# RAM.net
KiCad netlist of a schematic drawn in Altium Designer
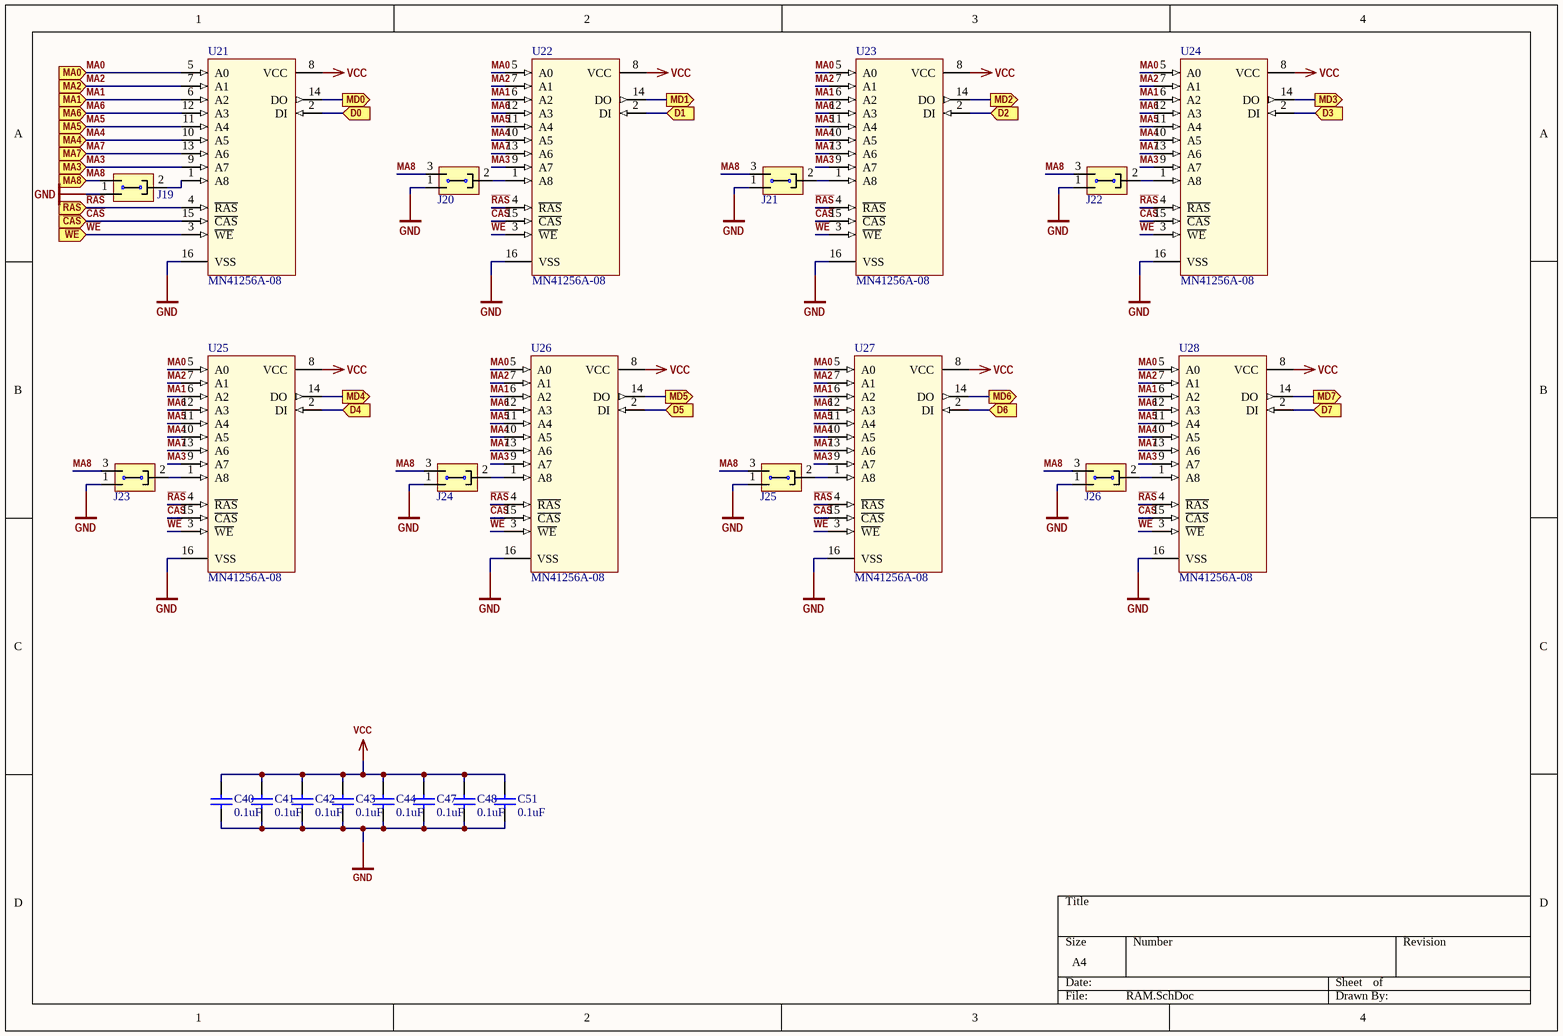
[diagram p0: RAM.SchDoc]

(export (version "E")
  (design (tool "Eeschema 10.0.6"))
  (components
    (comp (ref "C40")
      (value "0.1uF")
      (footprint "RAD-0.3")
      (description "Capacitor")
      (fields (field (name "Comment") "Cap") (field (name "PUBLISHER") "Altium Limited"))
      (libsource (lib "Lenin") (part "Cap"))
    )
    (comp (ref "C41")
      (value "0.1uF")
      (footprint "RAD-0.3")
      (description "Capacitor")
      (fields (field (name "Comment") "Cap") (field (name "PUBLISHER") "Altium Limited"))
      (libsource (lib "Lenin") (part "Cap"))
    )
    (comp (ref "C42")
      (value "0.1uF")
      (footprint "RAD-0.3")
      (description "Capacitor")
      (fields (field (name "Comment") "Cap") (field (name "PUBLISHER") "Altium Limited"))
      (libsource (lib "Lenin") (part "Cap"))
    )
    (comp (ref "C43")
      (value "0.1uF")
      (footprint "RAD-0.3")
      (description "Capacitor")
      (fields (field (name "Comment") "Cap") (field (name "PUBLISHER") "Altium Limited"))
      (libsource (lib "Lenin") (part "Cap"))
    )
    (comp (ref "C44")
      (value "0.1uF")
      (footprint "RAD-0.3")
      (description "Capacitor")
      (fields (field (name "Comment") "Cap") (field (name "PUBLISHER") "Altium Limited"))
      (libsource (lib "Lenin") (part "Cap"))
    )
    (comp (ref "C47")
      (value "0.1uF")
      (footprint "RAD-0.3")
      (description "Capacitor")
      (fields (field (name "Comment") "Cap") (field (name "PUBLISHER") "Altium Limited"))
      (libsource (lib "Lenin") (part "Cap"))
    )
    (comp (ref "C48")
      (value "0.1uF")
      (footprint "RAD-0.3")
      (description "Capacitor")
      (fields (field (name "Comment") "Cap") (field (name "PUBLISHER") "Altium Limited"))
      (libsource (lib "Lenin") (part "Cap"))
    )
    (comp (ref "C51")
      (value "0.1uF")
      (footprint "RAD-0.3")
      (description "Capacitor")
      (fields (field (name "Comment") "Cap") (field (name "PUBLISHER") "Altium Limited"))
      (libsource (lib "Lenin") (part "Cap"))
    )
    (comp (ref "J19")
      (value "Jump3")
      (footprint "Miscellaneous Connectors:MHDR1X3")
      (libsource (lib "Lenin") (part "Jump3"))
    )
    (comp (ref "J20")
      (value "Jump3")
      (footprint "Miscellaneous Connectors:MHDR1X3")
      (libsource (lib "Lenin") (part "Jump3"))
    )
    (comp (ref "J21")
      (value "Jump3")
      (footprint "Miscellaneous Connectors:MHDR1X3")
      (libsource (lib "Lenin") (part "Jump3"))
    )
    (comp (ref "J22")
      (value "Jump3")
      (footprint "Miscellaneous Connectors:MHDR1X3")
      (libsource (lib "Lenin") (part "Jump3"))
    )
    (comp (ref "J23")
      (value "Jump3")
      (footprint "Miscellaneous Connectors:MHDR1X3")
      (libsource (lib "Lenin") (part "Jump3"))
    )
    (comp (ref "J24")
      (value "Jump3")
      (footprint "Miscellaneous Connectors:MHDR1X3")
      (libsource (lib "Lenin") (part "Jump3"))
    )
    (comp (ref "J25")
      (value "Jump3")
      (footprint "Miscellaneous Connectors:MHDR1X3")
      (libsource (lib "Lenin") (part "Jump3"))
    )
    (comp (ref "J26")
      (value "Jump3")
      (footprint "Miscellaneous Connectors:MHDR1X3")
      (libsource (lib "Lenin") (part "Jump3"))
    )
    (comp (ref "U21")
      (value "MN41256A-08")
      (footprint "Panasonic:DIP16")
      (libsource (lib "Panasonic") (part "MN41256A-08"))
    )
    (comp (ref "U22")
      (value "MN41256A-08")
      (footprint "Panasonic:DIP16")
      (libsource (lib "Panasonic") (part "MN41256A-08"))
    )
    (comp (ref "U23")
      (value "MN41256A-08")
      (footprint "Panasonic:DIP16")
      (libsource (lib "Panasonic") (part "MN41256A-08"))
    )
    (comp (ref "U24")
      (value "MN41256A-08")
      (footprint "Panasonic:DIP16")
      (libsource (lib "Panasonic") (part "MN41256A-08"))
    )
    (comp (ref "U25")
      (value "MN41256A-08")
      (footprint "Panasonic:DIP16")
      (libsource (lib "Panasonic") (part "MN41256A-08"))
    )
    (comp (ref "U26")
      (value "MN41256A-08")
      (footprint "Panasonic:DIP16")
      (libsource (lib "Panasonic") (part "MN41256A-08"))
    )
    (comp (ref "U27")
      (value "MN41256A-08")
      (footprint "Panasonic:DIP16")
      (libsource (lib "Panasonic") (part "MN41256A-08"))
    )
    (comp (ref "U28")
      (value "MN41256A-08")
      (footprint "Panasonic:DIP16")
      (libsource (lib "Panasonic") (part "MN41256A-08"))
    )
  )
  (nets
    (net (code "1") (name "/D0") (class "Default")
      (node (ref "U21") (pin "2") (pinfunction "DI_2") (pintype "input"))
    )
    (net (code "2") (name "/D1") (class "Default")
      (node (ref "U22") (pin "2") (pinfunction "DI_2") (pintype "input"))
    )
    (net (code "3") (name "/D2") (class "Default")
      (node (ref "U23") (pin "2") (pinfunction "DI_2") (pintype "input"))
    )
    (net (code "4") (name "/D3") (class "Default")
      (node (ref "U24") (pin "2") (pinfunction "DI_2") (pintype "input"))
    )
    (net (code "5") (name "/D4") (class "Default")
      (node (ref "U25") (pin "2") (pinfunction "DI_2") (pintype "input"))
    )
    (net (code "6") (name "/D5") (class "Default")
      (node (ref "U26") (pin "2") (pinfunction "DI_2") (pintype "input"))
    )
    (net (code "7") (name "/D6") (class "Default")
      (node (ref "U27") (pin "2") (pinfunction "DI_2") (pintype "input"))
    )
    (net (code "8") (name "/D7") (class "Default")
      (node (ref "U28") (pin "2") (pinfunction "DI_2") (pintype "input"))
    )
    (net (code "9") (name "/MA0") (class "Default")
      (node (ref "U21") (pin "5") (pinfunction "A0_5") (pintype "input"))
      (node (ref "U22") (pin "5") (pinfunction "A0_5") (pintype "input"))
      (node (ref "U23") (pin "5") (pinfunction "A0_5") (pintype "input"))
      (node (ref "U24") (pin "5") (pinfunction "A0_5") (pintype "input"))
      (node (ref "U25") (pin "5") (pinfunction "A0_5") (pintype "input"))
      (node (ref "U26") (pin "5") (pinfunction "A0_5") (pintype "input"))
      (node (ref "U27") (pin "5") (pinfunction "A0_5") (pintype "input"))
      (node (ref "U28") (pin "5") (pinfunction "A0_5") (pintype "input"))
    )
    (net (code "10") (name "/MA1") (class "Default")
      (node (ref "U21") (pin "6") (pinfunction "A2_6") (pintype "input"))
      (node (ref "U22") (pin "6") (pinfunction "A2_6") (pintype "input"))
      (node (ref "U23") (pin "6") (pinfunction "A2_6") (pintype "input"))
      (node (ref "U24") (pin "6") (pinfunction "A2_6") (pintype "input"))
      (node (ref "U25") (pin "6") (pinfunction "A2_6") (pintype "input"))
      (node (ref "U26") (pin "6") (pinfunction "A2_6") (pintype "input"))
      (node (ref "U27") (pin "6") (pinfunction "A2_6") (pintype "input"))
      (node (ref "U28") (pin "6") (pinfunction "A2_6") (pintype "input"))
    )
    (net (code "11") (name "/MA2") (class "Default")
      (node (ref "U21") (pin "7") (pinfunction "A1_7") (pintype "input"))
      (node (ref "U22") (pin "7") (pinfunction "A1_7") (pintype "input"))
      (node (ref "U23") (pin "7") (pinfunction "A1_7") (pintype "input"))
      (node (ref "U24") (pin "7") (pinfunction "A1_7") (pintype "input"))
      (node (ref "U25") (pin "7") (pinfunction "A1_7") (pintype "input"))
      (node (ref "U26") (pin "7") (pinfunction "A1_7") (pintype "input"))
      (node (ref "U27") (pin "7") (pinfunction "A1_7") (pintype "input"))
      (node (ref "U28") (pin "7") (pinfunction "A1_7") (pintype "input"))
    )
    (net (code "12") (name "/MA3") (class "Default")
      (node (ref "U21") (pin "9") (pinfunction "A7_9") (pintype "input"))
      (node (ref "U22") (pin "9") (pinfunction "A7_9") (pintype "input"))
      (node (ref "U23") (pin "9") (pinfunction "A7_9") (pintype "input"))
      (node (ref "U24") (pin "9") (pinfunction "A7_9") (pintype "input"))
      (node (ref "U25") (pin "9") (pinfunction "A7_9") (pintype "input"))
      (node (ref "U26") (pin "9") (pinfunction "A7_9") (pintype "input"))
      (node (ref "U27") (pin "9") (pinfunction "A7_9") (pintype "input"))
      (node (ref "U28") (pin "9") (pinfunction "A7_9") (pintype "input"))
    )
    (net (code "13") (name "/MA4") (class "Default")
      (node (ref "U21") (pin "10") (pinfunction "A5_10") (pintype "input"))
      (node (ref "U22") (pin "10") (pinfunction "A5_10") (pintype "input"))
      (node (ref "U23") (pin "10") (pinfunction "A5_10") (pintype "input"))
      (node (ref "U24") (pin "10") (pinfunction "A5_10") (pintype "input"))
      (node (ref "U25") (pin "10") (pinfunction "A5_10") (pintype "input"))
      (node (ref "U26") (pin "10") (pinfunction "A5_10") (pintype "input"))
      (node (ref "U27") (pin "10") (pinfunction "A5_10") (pintype "input"))
      (node (ref "U28") (pin "10") (pinfunction "A5_10") (pintype "input"))
    )
    (net (code "14") (name "/MA5") (class "Default")
      (node (ref "U21") (pin "11") (pinfunction "A4_11") (pintype "input"))
      (node (ref "U22") (pin "11") (pinfunction "A4_11") (pintype "input"))
      (node (ref "U23") (pin "11") (pinfunction "A4_11") (pintype "input"))
      (node (ref "U24") (pin "11") (pinfunction "A4_11") (pintype "input"))
      (node (ref "U25") (pin "11") (pinfunction "A4_11") (pintype "input"))
      (node (ref "U26") (pin "11") (pinfunction "A4_11") (pintype "input"))
      (node (ref "U27") (pin "11") (pinfunction "A4_11") (pintype "input"))
      (node (ref "U28") (pin "11") (pinfunction "A4_11") (pintype "input"))
    )
    (net (code "15") (name "/MA6") (class "Default")
      (node (ref "U21") (pin "12") (pinfunction "A3_12") (pintype "input"))
      (node (ref "U22") (pin "12") (pinfunction "A3_12") (pintype "input"))
      (node (ref "U23") (pin "12") (pinfunction "A3_12") (pintype "input"))
      (node (ref "U24") (pin "12") (pinfunction "A3_12") (pintype "input"))
      (node (ref "U25") (pin "12") (pinfunction "A3_12") (pintype "input"))
      (node (ref "U26") (pin "12") (pinfunction "A3_12") (pintype "input"))
      (node (ref "U27") (pin "12") (pinfunction "A3_12") (pintype "input"))
      (node (ref "U28") (pin "12") (pinfunction "A3_12") (pintype "input"))
    )
    (net (code "16") (name "/MA7") (class "Default")
      (node (ref "U21") (pin "13") (pinfunction "A6_13") (pintype "input"))
      (node (ref "U22") (pin "13") (pinfunction "A6_13") (pintype "input"))
      (node (ref "U23") (pin "13") (pinfunction "A6_13") (pintype "input"))
      (node (ref "U24") (pin "13") (pinfunction "A6_13") (pintype "input"))
      (node (ref "U25") (pin "13") (pinfunction "A6_13") (pintype "input"))
      (node (ref "U26") (pin "13") (pinfunction "A6_13") (pintype "input"))
      (node (ref "U27") (pin "13") (pinfunction "A6_13") (pintype "input"))
      (node (ref "U28") (pin "13") (pinfunction "A6_13") (pintype "input"))
    )
    (net (code "17") (name "/MA8") (class "Default")
      (node (ref "J19") (pin "3") (pintype "passive"))
      (node (ref "J20") (pin "3") (pintype "passive"))
      (node (ref "J21") (pin "3") (pintype "passive"))
      (node (ref "J22") (pin "3") (pintype "passive"))
      (node (ref "J23") (pin "3") (pintype "passive"))
      (node (ref "J24") (pin "3") (pintype "passive"))
      (node (ref "J25") (pin "3") (pintype "passive"))
      (node (ref "J26") (pin "3") (pintype "passive"))
    )
    (net (code "18") (name "/MD0") (class "Default")
      (node (ref "U21") (pin "14") (pinfunction "DO_14") (pintype "output"))
    )
    (net (code "19") (name "/MD1") (class "Default")
      (node (ref "U22") (pin "14") (pinfunction "DO_14") (pintype "output"))
    )
    (net (code "20") (name "/MD2") (class "Default")
      (node (ref "U23") (pin "14") (pinfunction "DO_14") (pintype "output"))
    )
    (net (code "21") (name "/MD3") (class "Default")
      (node (ref "U24") (pin "14") (pinfunction "DO_14") (pintype "output"))
    )
    (net (code "22") (name "/MD4") (class "Default")
      (node (ref "U25") (pin "14") (pinfunction "DO_14") (pintype "output"))
    )
    (net (code "23") (name "/MD5") (class "Default")
      (node (ref "U26") (pin "14") (pinfunction "DO_14") (pintype "output"))
    )
    (net (code "24") (name "/MD6") (class "Default")
      (node (ref "U27") (pin "14") (pinfunction "DO_14") (pintype "output"))
    )
    (net (code "25") (name "/MD7") (class "Default")
      (node (ref "U28") (pin "14") (pinfunction "DO_14") (pintype "output"))
    )
    (net (code "26") (name "/~{CAS}") (class "Default")
      (node (ref "U21") (pin "15") (pinfunction "~{CAS}_15") (pintype "input"))
      (node (ref "U22") (pin "15") (pinfunction "~{CAS}_15") (pintype "input"))
      (node (ref "U23") (pin "15") (pinfunction "~{CAS}_15") (pintype "input"))
      (node (ref "U24") (pin "15") (pinfunction "~{CAS}_15") (pintype "input"))
      (node (ref "U25") (pin "15") (pinfunction "~{CAS}_15") (pintype "input"))
      (node (ref "U26") (pin "15") (pinfunction "~{CAS}_15") (pintype "input"))
      (node (ref "U27") (pin "15") (pinfunction "~{CAS}_15") (pintype "input"))
      (node (ref "U28") (pin "15") (pinfunction "~{CAS}_15") (pintype "input"))
    )
    (net (code "27") (name "/~{RAS}") (class "Default")
      (node (ref "U21") (pin "4") (pinfunction "~{RAS}_4") (pintype "input"))
      (node (ref "U22") (pin "4") (pinfunction "~{RAS}_4") (pintype "input"))
      (node (ref "U23") (pin "4") (pinfunction "~{RAS}_4") (pintype "input"))
      (node (ref "U24") (pin "4") (pinfunction "~{RAS}_4") (pintype "input"))
      (node (ref "U25") (pin "4") (pinfunction "~{RAS}_4") (pintype "input"))
      (node (ref "U26") (pin "4") (pinfunction "~{RAS}_4") (pintype "input"))
      (node (ref "U27") (pin "4") (pinfunction "~{RAS}_4") (pintype "input"))
      (node (ref "U28") (pin "4") (pinfunction "~{RAS}_4") (pintype "input"))
    )
    (net (code "28") (name "/~{WE}") (class "Default")
      (node (ref "U21") (pin "3") (pinfunction "~{WE}_3") (pintype "input"))
      (node (ref "U22") (pin "3") (pinfunction "~{WE}_3") (pintype "input"))
      (node (ref "U23") (pin "3") (pinfunction "~{WE}_3") (pintype "input"))
      (node (ref "U24") (pin "3") (pinfunction "~{WE}_3") (pintype "input"))
      (node (ref "U25") (pin "3") (pinfunction "~{WE}_3") (pintype "input"))
      (node (ref "U26") (pin "3") (pinfunction "~{WE}_3") (pintype "input"))
      (node (ref "U27") (pin "3") (pinfunction "~{WE}_3") (pintype "input"))
      (node (ref "U28") (pin "3") (pinfunction "~{WE}_3") (pintype "input"))
    )
    (net (code "29") (name "GND") (class "Default")
      (node (ref "C40") (pin "1") (pinfunction "1_1") (pintype "passive"))
      (node (ref "C41") (pin "1") (pinfunction "1_1") (pintype "passive"))
      (node (ref "C42") (pin "1") (pinfunction "1_1") (pintype "passive"))
      (node (ref "C43") (pin "1") (pinfunction "1_1") (pintype "passive"))
      (node (ref "C44") (pin "1") (pinfunction "1_1") (pintype "passive"))
      (node (ref "C47") (pin "1") (pinfunction "1_1") (pintype "passive"))
      (node (ref "C48") (pin "1") (pinfunction "1_1") (pintype "passive"))
      (node (ref "C51") (pin "1") (pinfunction "1_1") (pintype "passive"))
      (node (ref "J19") (pin "1") (pintype "passive"))
      (node (ref "J20") (pin "1") (pintype "passive"))
      (node (ref "J21") (pin "1") (pintype "passive"))
      (node (ref "J22") (pin "1") (pintype "passive"))
      (node (ref "J23") (pin "1") (pintype "passive"))
      (node (ref "J24") (pin "1") (pintype "passive"))
      (node (ref "J25") (pin "1") (pintype "passive"))
      (node (ref "J26") (pin "1") (pintype "passive"))
      (node (ref "U21") (pin "16") (pinfunction "VSS_16") (pintype "power_in"))
      (node (ref "U22") (pin "16") (pinfunction "VSS_16") (pintype "power_in"))
      (node (ref "U23") (pin "16") (pinfunction "VSS_16") (pintype "power_in"))
      (node (ref "U24") (pin "16") (pinfunction "VSS_16") (pintype "power_in"))
      (node (ref "U25") (pin "16") (pinfunction "VSS_16") (pintype "power_in"))
      (node (ref "U26") (pin "16") (pinfunction "VSS_16") (pintype "power_in"))
      (node (ref "U27") (pin "16") (pinfunction "VSS_16") (pintype "power_in"))
      (node (ref "U28") (pin "16") (pinfunction "VSS_16") (pintype "power_in"))
    )
    (net (code "30") (name "Net-(U21-A8)") (class "Default")
      (node (ref "J19") (pin "2") (pintype "passive"))
      (node (ref "U21") (pin "1") (pinfunction "A8_1") (pintype "input"))
    )
    (net (code "31") (name "Net-(U22-A8)") (class "Default")
      (node (ref "J20") (pin "2") (pintype "passive"))
      (node (ref "U22") (pin "1") (pinfunction "A8_1") (pintype "input"))
    )
    (net (code "32") (name "Net-(U23-A8)") (class "Default")
      (node (ref "J21") (pin "2") (pintype "passive"))
      (node (ref "U23") (pin "1") (pinfunction "A8_1") (pintype "input"))
    )
    (net (code "33") (name "Net-(U24-A8)") (class "Default")
      (node (ref "J22") (pin "2") (pintype "passive"))
      (node (ref "U24") (pin "1") (pinfunction "A8_1") (pintype "input"))
    )
    (net (code "34") (name "Net-(U25-A8)") (class "Default")
      (node (ref "J23") (pin "2") (pintype "passive"))
      (node (ref "U25") (pin "1") (pinfunction "A8_1") (pintype "input"))
    )
    (net (code "35") (name "Net-(U26-A8)") (class "Default")
      (node (ref "J24") (pin "2") (pintype "passive"))
      (node (ref "U26") (pin "1") (pinfunction "A8_1") (pintype "input"))
    )
    (net (code "36") (name "Net-(U27-A8)") (class "Default")
      (node (ref "J25") (pin "2") (pintype "passive"))
      (node (ref "U27") (pin "1") (pinfunction "A8_1") (pintype "input"))
    )
    (net (code "37") (name "Net-(U28-A8)") (class "Default")
      (node (ref "J26") (pin "2") (pintype "passive"))
      (node (ref "U28") (pin "1") (pinfunction "A8_1") (pintype "input"))
    )
    (net (code "38") (name "VCC") (class "Default")
      (node (ref "C40") (pin "2") (pinfunction "2_2") (pintype "passive"))
      (node (ref "C41") (pin "2") (pinfunction "2_2") (pintype "passive"))
      (node (ref "C42") (pin "2") (pinfunction "2_2") (pintype "passive"))
      (node (ref "C43") (pin "2") (pinfunction "2_2") (pintype "passive"))
      (node (ref "C44") (pin "2") (pinfunction "2_2") (pintype "passive"))
      (node (ref "C47") (pin "2") (pinfunction "2_2") (pintype "passive"))
      (node (ref "C48") (pin "2") (pinfunction "2_2") (pintype "passive"))
      (node (ref "C51") (pin "2") (pinfunction "2_2") (pintype "passive"))
      (node (ref "U21") (pin "8") (pinfunction "VCC_8") (pintype "power_in"))
      (node (ref "U22") (pin "8") (pinfunction "VCC_8") (pintype "power_in"))
      (node (ref "U23") (pin "8") (pinfunction "VCC_8") (pintype "power_in"))
      (node (ref "U24") (pin "8") (pinfunction "VCC_8") (pintype "power_in"))
      (node (ref "U25") (pin "8") (pinfunction "VCC_8") (pintype "power_in"))
      (node (ref "U26") (pin "8") (pinfunction "VCC_8") (pintype "power_in"))
      (node (ref "U27") (pin "8") (pinfunction "VCC_8") (pintype "power_in"))
      (node (ref "U28") (pin "8") (pinfunction "VCC_8") (pintype "power_in"))
    )
  )
)
